# DC12V_IN.net
KiCad netlist of a schematic drawn in Altium Designer
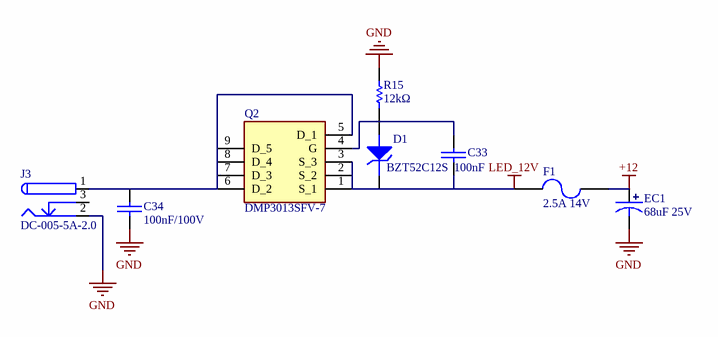
[diagram p0: DC12V_IN.SchDoc]

(export (version "E")
  (design (tool "Eeschema 10.0.6"))
  (components
    (comp (ref "C33")
      (value "100nF")
      (footprint "C_0603")
      (description "贴片电容")
      (libsource (lib "IntLib-Passive") (part "Cap_Chip"))
    )
    (comp (ref "C34")
      (value "100nF/100V")
      (footprint "C_0603")
      (description "贴片电容")
      (libsource (lib "IntLib-Passive") (part "Cap_Chip"))
    )
    (comp (ref "D1")
      (value "BZT52C12S")
      (footprint "SOD-323")
      (description "稳压二极管")
      (libsource (lib "IntLib-Active") (part "Diode_Zener"))
    )
    (comp (ref "EC1")
      (value "68uF 25V")
      (footprint "SMD-EC6.3X6.3X10")
      (description "贴片电解电容")
      (fields (field (name "MANUFACTURER_PART_NUMBER") "VZH680M1ETR-0606"))
      (libsource (lib "IntLib-Passive") (part "Cap_E_SMD"))
    )
    (comp (ref "F1")
      (value "2.5A 14V")
      (footprint "IntLib-Passive:Fuse_1812")
      (description "自恢复贴片保险丝")
      (fields (field (name "MANUFACTURER_PART_NUMBER") "TLC-MSMD250/14"))
      (libsource (lib "Passive-Fuse") (part "FUSE_PTC"))
    )
    (comp (ref "J3")
      (value "DC-005-5A-2.0")
      (footprint "DC-005")
      (description "DC电源座子")
      (libsource (lib "IntLib-Connector") (part "DC-Socket"))
    )
    (comp (ref "Q2")
      (value "DMP3013SFV-7")
      (footprint "SamacSys:DMP3013SFV7")
      (description "MOSFET (P-Channel)")
      (fields (field (name "MANUFACTURER_PART_NUMBER") "AP15P03Q"))
      (libsource (lib "*") (part "DMP3013SFV-7"))
    )
    (comp (ref "R15")
      (value "12kΩ")
      (footprint "R_0402")
      (description "贴片电阻")
      (libsource (lib "IntLib-Passive") (part "Res_Chip"))
    )
  )
  (nets
    (net (code "1") (name "+12") (class "Default")
      (node (ref "EC1") (pin "1") (pinfunction "1_1") (pintype "passive"))
      (node (ref "F1") (pin "2") (pinfunction "2_2") (pintype "passive"))
    )
    (net (code "2") (name "GND") (class "Default")
      (node (ref "C34") (pin "1") (pinfunction "1_1") (pintype "passive"))
      (node (ref "EC1") (pin "2") (pinfunction "2_2") (pintype "passive"))
      (node (ref "J3") (pin "2") (pinfunction "2_2") (pintype "power_in"))
      (node (ref "R15") (pin "1") (pinfunction "1_1") (pintype "passive"))
    )
    (net (code "3") (name "LED_12V") (class "Default")
      (node (ref "C33") (pin "1") (pinfunction "1_1") (pintype "passive"))
      (node (ref "D1") (pin "K") (pinfunction "K_K") (pintype "passive"))
      (node (ref "F1") (pin "1") (pinfunction "1_1") (pintype "passive"))
      (node (ref "Q2") (pin "1") (pinfunction "S_1_1") (pintype "passive"))
      (node (ref "Q2") (pin "2") (pinfunction "S_2_2") (pintype "passive"))
      (node (ref "Q2") (pin "3") (pinfunction "S_3_3") (pintype "passive"))
    )
    (net (code "4") (name "Net-(Q2-D_1)") (class "Default")
      (node (ref "C34") (pin "2") (pinfunction "2_2") (pintype "passive"))
      (node (ref "J3") (pin "1") (pinfunction "1_1") (pintype "power_in"))
      (node (ref "Q2") (pin "5") (pinfunction "D_1_5") (pintype "passive"))
      (node (ref "Q2") (pin "6") (pinfunction "D_2_6") (pintype "passive"))
      (node (ref "Q2") (pin "7") (pinfunction "D_3_7") (pintype "passive"))
      (node (ref "Q2") (pin "8") (pinfunction "D_4_8") (pintype "passive"))
      (node (ref "Q2") (pin "9") (pinfunction "D_5_9") (pintype "passive"))
    )
    (net (code "5") (name "Net-(Q2-G)") (class "Default")
      (node (ref "C33") (pin "2") (pinfunction "2_2") (pintype "passive"))
      (node (ref "D1") (pin "A") (pinfunction "A_A") (pintype "passive"))
      (node (ref "Q2") (pin "4") (pinfunction "G_4") (pintype "passive"))
      (node (ref "R15") (pin "2") (pinfunction "2_2") (pintype "passive"))
    )
    (net (code "6") (name "unconnected-(J3-Pad3)") (class "Default")
      (node (ref "J3") (pin "3") (pinfunction "3_3") (pintype "power_in"))
    )
  )
)
